# TinkerAccess_Remote_RFID.net
KiCad netlist of a schematic drawn in EAGLE
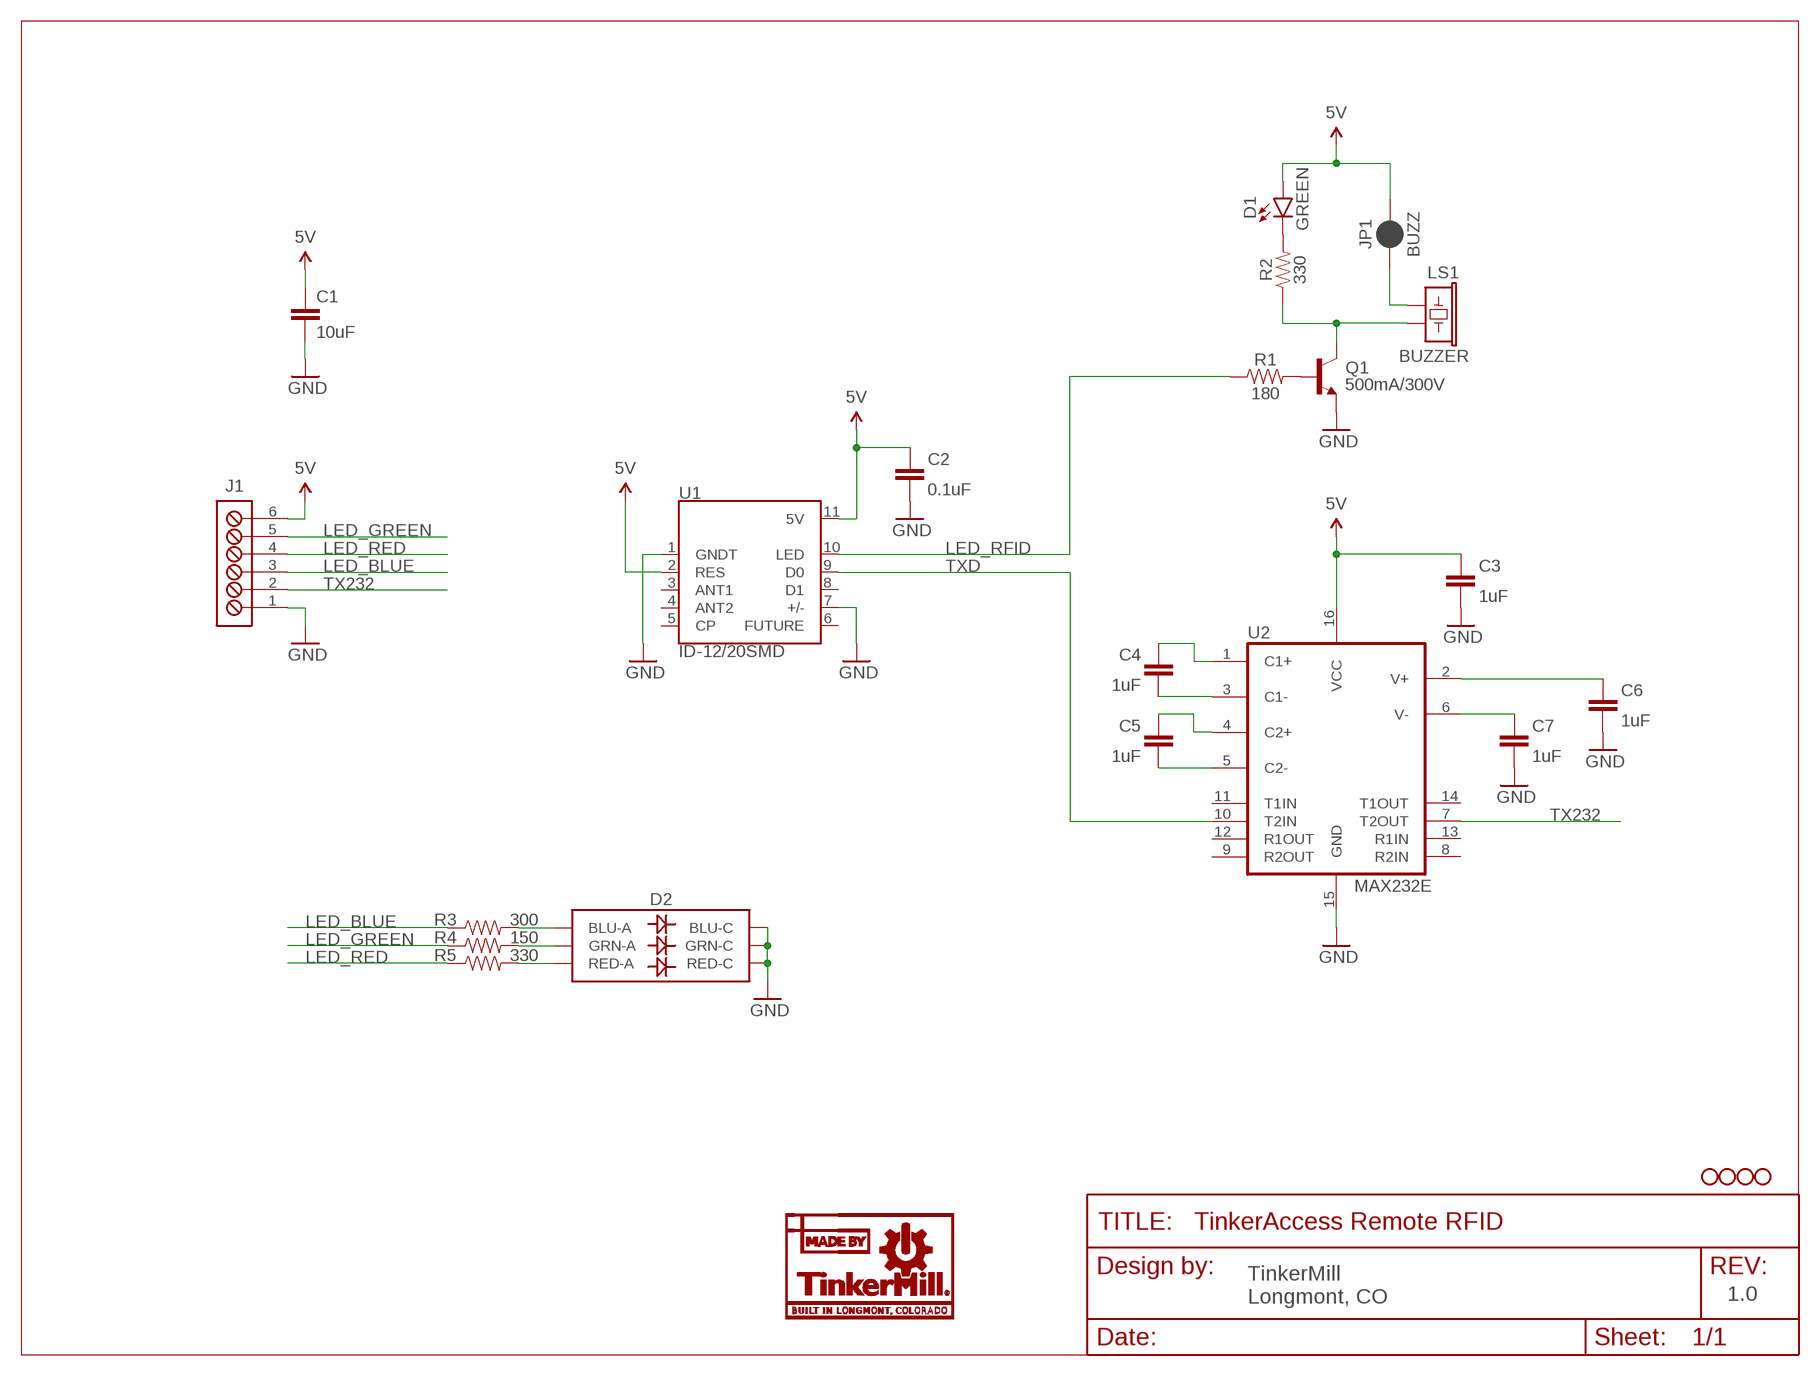
[diagram p0: schematic, sheet 1]

(export (version "E")
  (design (tool "Eeschema 10.0.6"))
  (components
    (comp (ref "C1")
      (value "10uF")
      (footprint "eagle-import:1206")
      (libsource (lib "eagle-import") (part "10UF-1206-6.3V-20%"))
    )
    (comp (ref "C2")
      (value "0.1uF")
      (footprint "eagle-import:0603")
      (libsource (lib "eagle-import") (part "0.1UF-0603-25V-(+80/-20%)"))
    )
    (comp (ref "C3")
      (value "1uF")
      (footprint "eagle-import:0603")
      (libsource (lib "eagle-import") (part "0.1UF-0603-25V-(+80/-20%)"))
    )
    (comp (ref "C4")
      (value "1uF")
      (footprint "eagle-import:0603")
      (libsource (lib "eagle-import") (part "0.1UF-0603-25V-(+80/-20%)"))
    )
    (comp (ref "C5")
      (value "1uF")
      (footprint "eagle-import:0603")
      (libsource (lib "eagle-import") (part "0.1UF-0603-25V-(+80/-20%)"))
    )
    (comp (ref "C6")
      (value "1uF")
      (footprint "eagle-import:0603")
      (libsource (lib "eagle-import") (part "0.1UF-0603-25V-(+80/-20%)"))
    )
    (comp (ref "C7")
      (value "1uF")
      (footprint "eagle-import:0603")
      (libsource (lib "eagle-import") (part "0.1UF-0603-25V-(+80/-20%)"))
    )
    (comp (ref "D1")
      (value "GREEN")
      (footprint "eagle-import:LED-1206")
      (libsource (lib "eagle-import") (part "LED-GREEN1206"))
    )
    (comp (ref "D2")
      (value "LED-RGBNO_IC")
      (footprint "eagle-import:LED-TRICOLOR-5050")
      (libsource (lib "eagle-import") (part "LED-RGBNO_IC"))
    )
    (comp (ref "J1")
      (value "TB_6X1_TE_CONN_ED555_6DS")
      (footprint "eagle-import:TE_CONN_ED555_6DS")
      (libsource (lib "eagle-import") (part "TB_6X1_TE_CONN_ED555_6DS"))
    )
    (comp (ref "JP1")
      (value "BUZZ")
      (footprint "eagle-import:SMT-JUMPER_2_NC_PASTE_NO-SILK")
      (libsource (lib "eagle-import") (part "JUMPER-SMT_2_NC_PASTE_NO-SILK"))
    )
    (comp (ref "LOGO1")
      (value "MADE_BY_TINKERMILL")
      (footprint "eagle-import:MADE_BY_TINKERMILL")
      (libsource (lib "eagle-import") (part "MADE_BY_TINKERMILL"))
    )
    (comp (ref "LS1")
      (value "BUZZER")
      (footprint "eagle-import:BUZZER-CCV")
      (libsource (lib "eagle-import") (part "BUZZER-SMD"))
    )
    (comp (ref "Q1")
      (value "500mA/300V")
      (footprint "eagle-import:SOT23-3")
      (libsource (lib "eagle-import") (part "TRANS_NPN-MMBTA42"))
    )
    (comp (ref "R1")
      (value "180")
      (footprint "eagle-import:0603")
      (libsource (lib "eagle-import") (part "10MOHM-0603-1/10W-5%"))
    )
    (comp (ref "R2")
      (value "330")
      (footprint "eagle-import:0603")
      (libsource (lib "eagle-import") (part "10MOHM-0603-1/10W-5%"))
    )
    (comp (ref "R3")
      (value "300")
      (footprint "eagle-import:0603")
      (libsource (lib "eagle-import") (part "300OHM-0603-1/10W-1%"))
    )
    (comp (ref "R4")
      (value "150")
      (footprint "eagle-import:0603")
      (libsource (lib "eagle-import") (part "150OHM-0603-1/10W-1%"))
    )
    (comp (ref "R5")
      (value "330")
      (footprint "eagle-import:0603")
      (libsource (lib "eagle-import") (part "330OHM-0603-1/10W-1%"))
    )
    (comp (ref "STANDOFF1")
      (value "STANDOFF_3.2MM_NO_CU_MASK")
      (footprint "eagle-import:STANDOFF_3.2MM_NO_CU_MASK")
      (libsource (lib "eagle-import") (part "STANDOFF_3.2MM_NO_CU_MASK"))
    )
    (comp (ref "STANDOFF2")
      (value "STANDOFF_3.2MM_NO_CU_MASK")
      (footprint "eagle-import:STANDOFF_3.2MM_NO_CU_MASK")
      (libsource (lib "eagle-import") (part "STANDOFF_3.2MM_NO_CU_MASK"))
    )
    (comp (ref "STANDOFF3")
      (value "STANDOFF_3.2MM_NO_CU_MASK")
      (footprint "eagle-import:STANDOFF_3.2MM_NO_CU_MASK")
      (libsource (lib "eagle-import") (part "STANDOFF_3.2MM_NO_CU_MASK"))
    )
    (comp (ref "STANDOFF4")
      (value "STANDOFF_3.2MM_NO_CU_MASK")
      (footprint "eagle-import:STANDOFF_3.2MM_NO_CU_MASK")
      (libsource (lib "eagle-import") (part "STANDOFF_3.2MM_NO_CU_MASK"))
    )
    (comp (ref "U1")
      (value "ID-12/20SMD")
      (footprint "eagle-import:ID-12_SMD")
      (libsource (lib "eagle-import") (part "ID-12/20SMD"))
    )
    (comp (ref "U2")
      (value "MAX232E")
      (footprint "eagle-import:TSSOP16")
      (libsource (lib "eagle-import") (part "MAX232TSSOP"))
    )
  )
  (nets
    (net (code "1") (name "/LED_BLUE") (class "Default")
      (node (ref "J1") (pin "3") (pinfunction "3_3") (pintype "passive"))
      (node (ref "R3") (pin "1") (pinfunction "1_1") (pintype "passive"))
    )
    (net (code "2") (name "/LED_GREEN") (class "Default")
      (node (ref "J1") (pin "5") (pinfunction "5_5") (pintype "passive"))
      (node (ref "R4") (pin "1") (pinfunction "1_1") (pintype "passive"))
    )
    (net (code "3") (name "/LED_RED") (class "Default")
      (node (ref "J1") (pin "4") (pinfunction "4_4") (pintype "passive"))
      (node (ref "R5") (pin "1") (pinfunction "1_1") (pintype "passive"))
    )
    (net (code "4") (name "/LED_RFID") (class "Default")
      (node (ref "R1") (pin "1") (pinfunction "1_1") (pintype "passive"))
      (node (ref "U1") (pin "10") (pinfunction "LED_10") (pintype "bidirectional"))
    )
    (net (code "5") (name "/TX232") (class "Default")
      (node (ref "J1") (pin "2") (pinfunction "2_2") (pintype "passive"))
      (node (ref "U2") (pin "7") (pinfunction "T2OUT_7") (pintype "output"))
    )
    (net (code "6") (name "/TXD") (class "Default")
      (node (ref "U1") (pin "9") (pinfunction "D0_9") (pintype "bidirectional"))
      (node (ref "U2") (pin "10") (pinfunction "T2IN_10") (pintype "input"))
    )
    (net (code "7") (name "5V") (class "Default")
      (node (ref "C1") (pin "1") (pinfunction "1_1") (pintype "passive"))
      (node (ref "C2") (pin "2") (pinfunction "2_2") (pintype "passive"))
      (node (ref "C3") (pin "2") (pinfunction "2_2") (pintype "passive"))
      (node (ref "D1") (pin "A") (pinfunction "A_A") (pintype "passive"))
      (node (ref "J1") (pin "6") (pinfunction "6_6") (pintype "passive"))
      (node (ref "JP1") (pin "2") (pinfunction "2_2") (pintype "passive"))
      (node (ref "U1") (pin "11") (pinfunction "5V_11") (pintype "bidirectional"))
      (node (ref "U1") (pin "2") (pinfunction "RES_2") (pintype "bidirectional"))
      (node (ref "U2") (pin "16") (pinfunction "VCC_16") (pintype "bidirectional"))
    )
    (net (code "8") (name "GND") (class "Default")
      (node (ref "C1") (pin "2") (pinfunction "2_2") (pintype "passive"))
      (node (ref "C2") (pin "1") (pinfunction "1_1") (pintype "passive"))
      (node (ref "C3") (pin "1") (pinfunction "1_1") (pintype "passive"))
      (node (ref "C6") (pin "1") (pinfunction "1_1") (pintype "passive"))
      (node (ref "C7") (pin "1") (pinfunction "1_1") (pintype "passive"))
      (node (ref "D2") (pin "4") (pinfunction "BLU-C_4") (pintype "bidirectional"))
      (node (ref "D2") (pin "5") (pinfunction "RED-C_5") (pintype "bidirectional"))
      (node (ref "D2") (pin "6") (pinfunction "GRN-C_6") (pintype "bidirectional"))
      (node (ref "J1") (pin "1") (pinfunction "1_1") (pintype "passive"))
      (node (ref "Q1") (pin "2") (pinfunction "E_2") (pintype "passive"))
      (node (ref "U1") (pin "1") (pinfunction "GNDT_1") (pintype "bidirectional"))
      (node (ref "U1") (pin "7") (pinfunction "+/-_7") (pintype "bidirectional"))
      (node (ref "U2") (pin "15") (pinfunction "GND_15") (pintype "bidirectional"))
    )
    (net (code "9") (name "Net-(D1-PadC)") (class "Default")
      (node (ref "D1") (pin "C") (pinfunction "C_C") (pintype "passive"))
      (node (ref "R2") (pin "2") (pinfunction "2_2") (pintype "passive"))
    )
    (net (code "10") (name "Net-(D2-BLU-A)") (class "Default")
      (node (ref "D2") (pin "3") (pinfunction "BLU-A_3") (pintype "bidirectional"))
      (node (ref "R3") (pin "2") (pinfunction "2_2") (pintype "passive"))
    )
    (net (code "11") (name "Net-(D2-GRN-A)") (class "Default")
      (node (ref "D2") (pin "1") (pinfunction "GRN-A_1") (pintype "bidirectional"))
      (node (ref "R4") (pin "2") (pinfunction "2_2") (pintype "passive"))
    )
    (net (code "12") (name "Net-(D2-RED-A)") (class "Default")
      (node (ref "D2") (pin "2") (pinfunction "RED-A_2") (pintype "bidirectional"))
      (node (ref "R5") (pin "2") (pinfunction "2_2") (pintype "passive"))
    )
    (net (code "13") (name "Net-(LS1-1)") (class "Default")
      (node (ref "JP1") (pin "1") (pinfunction "1_1") (pintype "passive"))
      (node (ref "LS1") (pin "+") (pinfunction "1_+") (pintype "passive"))
    )
    (net (code "14") (name "Net-(LS1-2)") (class "Default")
      (node (ref "LS1") (pin "-") (pinfunction "2_-") (pintype "passive"))
      (node (ref "Q1") (pin "3") (pinfunction "C_3") (pintype "passive"))
      (node (ref "R2") (pin "1") (pinfunction "1_1") (pintype "passive"))
    )
    (net (code "15") (name "Net-(Q1-B)") (class "Default")
      (node (ref "Q1") (pin "1") (pinfunction "B_1") (pintype "passive"))
      (node (ref "R1") (pin "2") (pinfunction "2_2") (pintype "passive"))
    )
    (net (code "16") (name "Net-(U2-C1+)") (class "Default")
      (node (ref "C4") (pin "2") (pinfunction "2_2") (pintype "passive"))
      (node (ref "U2") (pin "1") (pinfunction "C1+_1") (pintype "bidirectional"))
    )
    (net (code "17") (name "Net-(U2-C1-)") (class "Default")
      (node (ref "C4") (pin "1") (pinfunction "1_1") (pintype "passive"))
      (node (ref "U2") (pin "3") (pinfunction "C1-_3") (pintype "bidirectional"))
    )
    (net (code "18") (name "Net-(U2-C2+)") (class "Default")
      (node (ref "C5") (pin "2") (pinfunction "2_2") (pintype "passive"))
      (node (ref "U2") (pin "4") (pinfunction "C2+_4") (pintype "bidirectional"))
    )
    (net (code "19") (name "Net-(U2-C2-)") (class "Default")
      (node (ref "C5") (pin "1") (pinfunction "1_1") (pintype "passive"))
      (node (ref "U2") (pin "5") (pinfunction "C2-_5") (pintype "bidirectional"))
    )
    (net (code "20") (name "Net-(U2-V+)") (class "Default")
      (node (ref "C6") (pin "2") (pinfunction "2_2") (pintype "passive"))
      (node (ref "U2") (pin "2") (pinfunction "V+_2") (pintype "bidirectional"))
    )
    (net (code "21") (name "Net-(U2-V-)") (class "Default")
      (node (ref "C7") (pin "2") (pinfunction "2_2") (pintype "passive"))
      (node (ref "U2") (pin "6") (pinfunction "V-_6") (pintype "bidirectional"))
    )
    (net (code "22") (name "unconnected-(U1-ANT1-Pad3)") (class "Default")
      (node (ref "U1") (pin "3") (pinfunction "ANT1_3") (pintype "bidirectional"))
    )
    (net (code "23") (name "unconnected-(U1-ANT2-Pad4)") (class "Default")
      (node (ref "U1") (pin "4") (pinfunction "ANT2_4") (pintype "bidirectional"))
    )
    (net (code "24") (name "unconnected-(U1-CP-Pad5)") (class "Default")
      (node (ref "U1") (pin "5") (pinfunction "CP_5") (pintype "bidirectional"))
    )
    (net (code "25") (name "unconnected-(U1-D1-Pad8)") (class "Default")
      (node (ref "U1") (pin "8") (pinfunction "D1_8") (pintype "bidirectional"))
    )
    (net (code "26") (name "unconnected-(U1-FUTURE-Pad6)") (class "Default")
      (node (ref "U1") (pin "6") (pinfunction "FUTURE_6") (pintype "bidirectional"))
    )
    (net (code "27") (name "unconnected-(U2-R1IN-Pad13)") (class "Default")
      (node (ref "U2") (pin "13") (pinfunction "R1IN_13") (pintype "input"))
    )
    (net (code "28") (name "unconnected-(U2-R1OUT-Pad12)") (class "Default")
      (node (ref "U2") (pin "12") (pinfunction "R1OUT_12") (pintype "output"))
    )
    (net (code "29") (name "unconnected-(U2-R2IN-Pad8)") (class "Default")
      (node (ref "U2") (pin "8") (pinfunction "R2IN_8") (pintype "input"))
    )
    (net (code "30") (name "unconnected-(U2-R2OUT-Pad9)") (class "Default")
      (node (ref "U2") (pin "9") (pinfunction "R2OUT_9") (pintype "output"))
    )
    (net (code "31") (name "unconnected-(U2-T1IN-Pad11)") (class "Default")
      (node (ref "U2") (pin "11") (pinfunction "T1IN_11") (pintype "input"))
    )
    (net (code "32") (name "unconnected-(U2-T1OUT-Pad14)") (class "Default")
      (node (ref "U2") (pin "14") (pinfunction "T1OUT_14") (pintype "output"))
    )
  )
)
